# merigold.net
KiCad netlist of a schematic drawn in Altium Designer
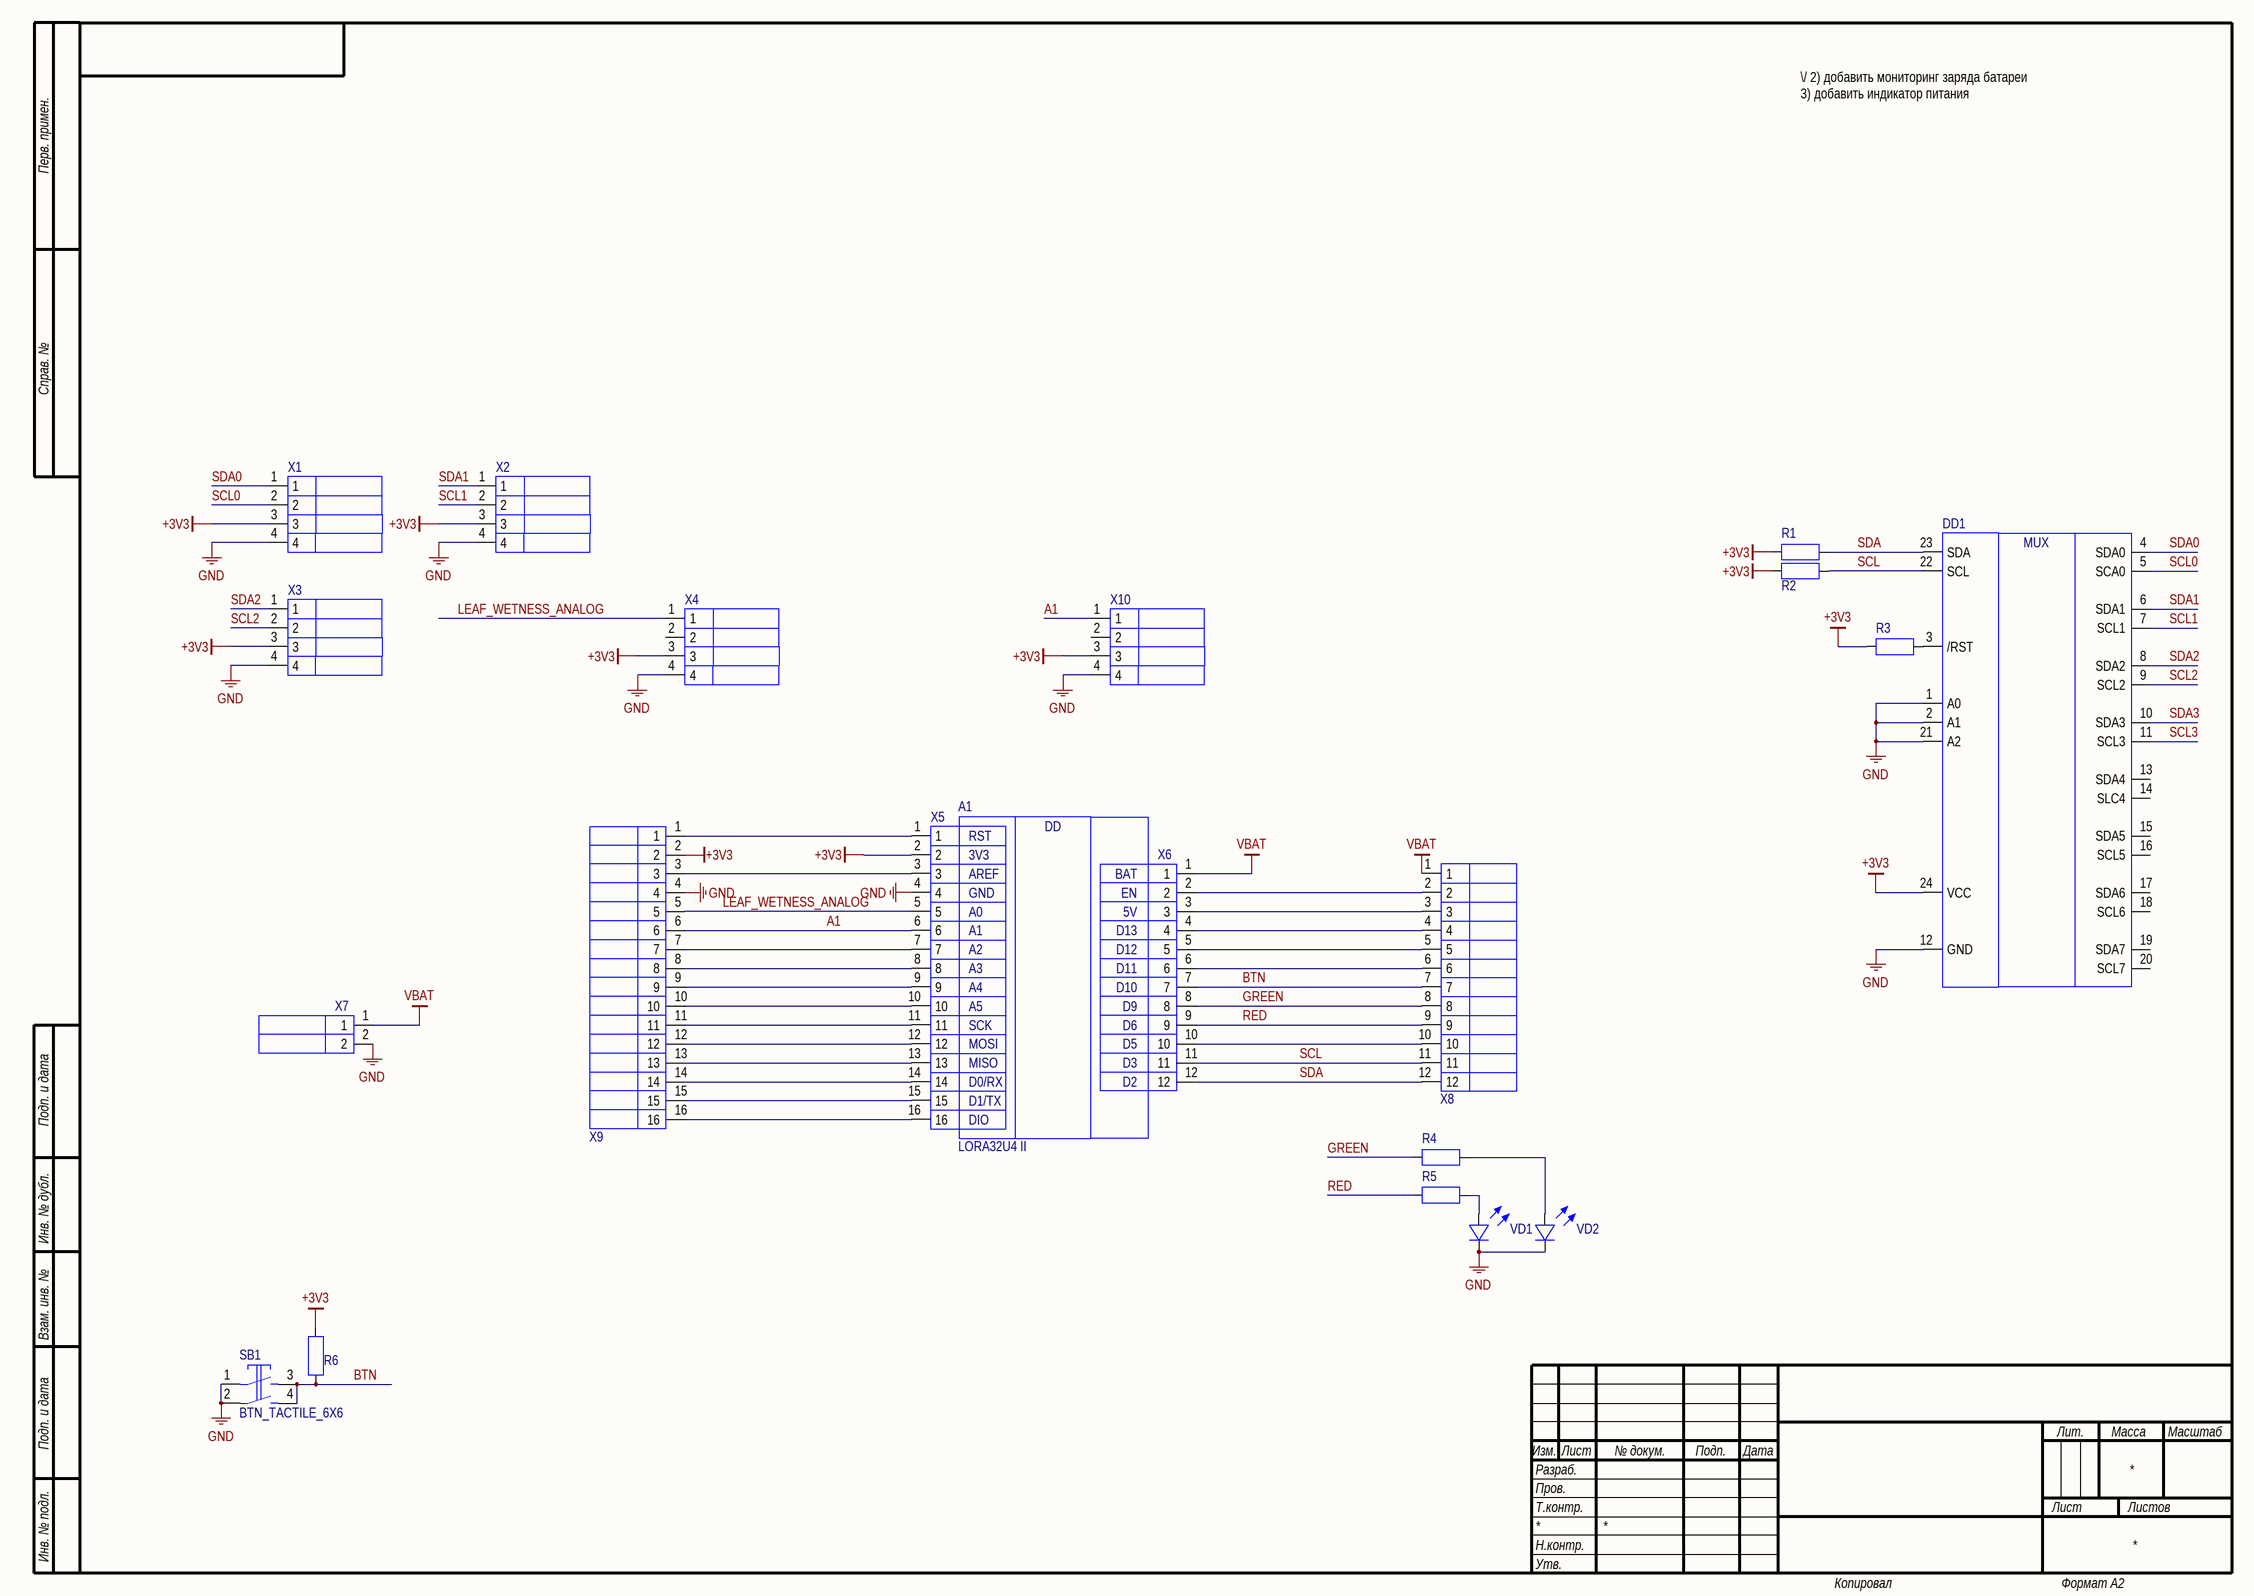
[diagram p0: merigold.SchDoc]

(export (version "E")
  (design (tool "Eeschema 10.0.6"))
  (components
    (comp (ref "A1")
      (value "LORA32U4 II")
      (footprint "LORA32U4 II")
      (description "LORA 32U4 II 868MHZ")
      (fields
        (field (name "MANUFACTURER") "BSFrance")
        (field (name "MANUFACTURER PART NUMBER") "Lora32U4 II ver 1.2")
      )
      (libsource (lib "EVALBRD") (part "LORA32U4 II"))
    )
    (comp (ref "DD1")
      (value "TCA9548A")
      (footprint "TSOP65P640X120-24M")
      (description "IC I2C SW 8CH W/RESET 24TSSOP")
      (fields
        (field (name "MANUFACTURER") "Texas Instruments")
        (field (name "MANUFACTURER PART NUMBER") "TCA9548APWR")
      )
      (libsource (lib "IC") (part "TCA9548A"))
    )
    (comp (ref "R1")
      (value "10K1206")
      (footprint "RLC:RESC3216X07N/1206")
      (description "RES SMD 10K OHM 1% 1/4W 1206")
      (fields
        (field (name "MANUFACTURER") "Panasonic")
        (field (name "MANUFACTURER PART NUMBER") "ERJ8ENF1002V")
      )
      (libsource (lib "") (part "10K1206_1"))
    )
    (comp (ref "R2")
      (value "10K1206")
      (footprint "RLC:RESC3216X07N/1206")
      (description "RES SMD 10K OHM 1% 1/4W 1206")
      (fields
        (field (name "MANUFACTURER") "Panasonic")
        (field (name "MANUFACTURER PART NUMBER") "ERJ8ENF1002V")
      )
      (libsource (lib "") (part "10K1206_1"))
    )
    (comp (ref "R3")
      (value "10K1206")
      (footprint "RLC:RESC3216X07N/1206")
      (description "RES SMD 10K OHM 1% 1/4W 1206")
      (fields
        (field (name "MANUFACTURER") "Panasonic")
        (field (name "MANUFACTURER PART NUMBER") "ERJ8ENF1002V")
      )
      (libsource (lib "") (part "10K1206_1"))
    )
    (comp (ref "R4")
      (value "200R1206")
      (footprint "RESC3216X07N/1206")
      (description "RES SMD 200 OHM 1% 1/4W 1206")
      (fields
        (field (name "MANUFACTURER PART NUMBER") "CRCW1206200RFKEA")
        (field (name "MANUFACTURER") "Vishay Dale")
      )
      (libsource (lib "R") (part "200R1206"))
    )
    (comp (ref "R5")
      (value "200R1206")
      (footprint "RESC3216X07N/1206")
      (description "RES SMD 200 OHM 1% 1/4W 1206")
      (fields
        (field (name "MANUFACTURER PART NUMBER") "CRCW1206200RFKEA")
        (field (name "MANUFACTURER") "Vishay Dale")
      )
      (libsource (lib "R") (part "200R1206"))
    )
    (comp (ref "R6")
      (value "10K1206")
      (footprint "RLC:RESC3216X07N/1206")
      (description "RES SMD 10K OHM 1% 1/4W 1206")
      (fields
        (field (name "MANUFACTURER") "Panasonic")
        (field (name "MANUFACTURER PART NUMBER") "ERJ8ENF1002V")
      )
      (libsource (lib "R") (part "10K1206"))
    )
    (comp (ref "SB1")
      (value "BTN_TACTILE_6X6")
      (footprint "BTN_TACTILE_6X6")
      (description "SWITCH TACTILE SPST-NO 0.05A 24V")
      (fields
        (field (name "MANUFACTURER") "TE Connectivity Alcoswitch")
        (field (name "MANUFACTURER PART NUMBER") "1825910-6")
      )
      (libsource (lib "SW") (part "BTN_TACTILE_6X6"))
    )
    (comp (ref "VD1")
      (value "LED_SSL-LX5093GD-TR26")
      (footprint "LED500")
      (description "LED GREEN DIFFUSED T-1 3/4 T/H")
      (fields
        (field (name "MANUFACTURER") "Lumex")
        (field (name "MANUFACTURER PART NUMBER") "SSL-LX5093GD-TR26")
      )
      (libsource (lib "D") (part "LED_SSL-LX5093GD-TR26"))
    )
    (comp (ref "VD2")
      (value "LED_SSL-LX5093GD-TR26")
      (footprint "LED500")
      (description "LED GREEN DIFFUSED T-1 3/4 T/H")
      (fields
        (field (name "MANUFACTURER") "Lumex")
        (field (name "MANUFACTURER PART NUMBER") "SSL-LX5093GD-TR26")
      )
      (libsource (lib "D") (part "LED_SSL-LX5093GD-TR26"))
    )
    (comp (ref "X1")
      (value "MOLEX_0397000904")
      (footprint "MOLEX_0397000904")
      (description "TERM BLK 4POS TOP ENTRY 5MM PCB")
      (fields (field (name "MANUFACTURER") "Molex") (field (name "MANUFACTURER PART NUMBER") "0397000904"))
      (libsource (lib "X") (part "MOLEX_0397000904"))
    )
    (comp (ref "X2")
      (value "MOLEX_0397000904")
      (footprint "MOLEX_0397000904")
      (description "TERM BLK 4POS TOP ENTRY 5MM PCB")
      (fields (field (name "MANUFACTURER") "Molex") (field (name "MANUFACTURER PART NUMBER") "0397000904"))
      (libsource (lib "X") (part "MOLEX_0397000904"))
    )
    (comp (ref "X3")
      (value "MOLEX_0397000904")
      (footprint "MOLEX_0397000904")
      (description "TERM BLK 4POS TOP ENTRY 5MM PCB")
      (fields (field (name "MANUFACTURER") "Molex") (field (name "MANUFACTURER PART NUMBER") "0397000904"))
      (libsource (lib "X") (part "MOLEX_0397000904"))
    )
    (comp (ref "X4")
      (value "MOLEX_0397000904")
      (footprint "MOLEX_0397000904")
      (description "TERM BLK 4POS TOP ENTRY 5MM PCB")
      (fields (field (name "MANUFACTURER") "Molex") (field (name "MANUFACTURER PART NUMBER") "0397000904"))
      (libsource (lib "X") (part "MOLEX_0397000904"))
    )
    (comp (ref "X5")
      (value "PLS_16_FEMALE")
      (footprint "PLS_16_FEMALE")
      (description "CONN RCPT 16POS 0.1 GOLD PCB")
      (fields
        (field (name "MANUFACTURER") "TE Connectivity AMP Connectors")
        (field (name "MANUFACTURER PART NUMBER") "1-534237-4")
      )
      (libsource (lib "X") (part "PLS_16_FEMALE"))
    )
    (comp (ref "X6")
      (value "PLS_12_FEMALE")
      (footprint "PLS_12_FEMALE")
      (description "CONN RCPT 12POS 0.1 GOLD PCB")
      (fields
        (field (name "MANUFACTURER") "TE Connectivity AMP Connectors")
        (field (name "MANUFACTURER PART NUMBER") "1-534237-0")
      )
      (libsource (lib "X") (part "PLS_12_FEMALE"))
    )
    (comp (ref "X7")
      (value "2EDGV-5.0-02P")
      (footprint "2EDGV-5.0-02P")
      (description "TERM BLOCK HDR 2POS VERT 5MM")
      (fields
        (field (name "MANUFACTURER") "Phoenix Contact")
        (field (name "MANUFACTURER PART NUMBER") "1753437")
      )
      (libsource (lib "X") (part "2EDGV-5.0-02P"))
    )
    (comp (ref "X8")
      (value "PLS_12_FEMALE")
      (footprint "PLS_12_FEMALE")
      (description "CONN RCPT 12POS 0.1 GOLD PCB")
      (fields
        (field (name "MANUFACTURER") "TE Connectivity AMP Connectors")
        (field (name "MANUFACTURER PART NUMBER") "1-534237-0")
      )
      (libsource (lib "X") (part "PLS_12_FEMALE"))
    )
    (comp (ref "X9")
      (value "PLS_16_FEMALE")
      (footprint "PLS_16_FEMALE")
      (description "CONN RCPT 16POS 0.1 GOLD PCB")
      (fields
        (field (name "MANUFACTURER") "TE Connectivity AMP Connectors")
        (field (name "MANUFACTURER PART NUMBER") "1-534237-4")
      )
      (libsource (lib "X") (part "PLS_16_FEMALE"))
    )
    (comp (ref "X10")
      (value "MOLEX_0397000904")
      (footprint "MOLEX_0397000904")
      (description "TERM BLK 4POS TOP ENTRY 5MM PCB")
      (fields (field (name "MANUFACTURER") "Molex") (field (name "MANUFACTURER PART NUMBER") "0397000904"))
      (libsource (lib "X") (part "MOLEX_0397000904"))
    )
  )
  (nets
    (net (code "1") (name "+3V3") (class "Default")
      (node (ref "DD1") (pin "24") (pinfunction "VCC_24") (pintype "passive"))
      (node (ref "R1") (pin "2") (pinfunction "2_2") (pintype "passive"))
      (node (ref "R2") (pin "2") (pinfunction "2_2") (pintype "passive"))
      (node (ref "R3") (pin "2") (pinfunction "2_2") (pintype "passive"))
      (node (ref "R6") (pin "2") (pinfunction "2_2") (pintype "passive"))
      (node (ref "X1") (pin "3") (pinfunction "3_3") (pintype "passive"))
      (node (ref "X10") (pin "3") (pinfunction "3_3") (pintype "passive"))
      (node (ref "X2") (pin "3") (pinfunction "3_3") (pintype "passive"))
      (node (ref "X3") (pin "3") (pinfunction "3_3") (pintype "passive"))
      (node (ref "X4") (pin "3") (pinfunction "3_3") (pintype "passive"))
      (node (ref "X5") (pin "2") (pinfunction "2_2") (pintype "passive"))
      (node (ref "X9") (pin "2") (pinfunction "2_2") (pintype "passive"))
    )
    (net (code "2") (name "/A1") (class "Default")
      (node (ref "X10") (pin "1") (pinfunction "1_1") (pintype "passive"))
      (node (ref "X5") (pin "6") (pinfunction "6_6") (pintype "passive"))
      (node (ref "X9") (pin "6") (pinfunction "6_6") (pintype "passive"))
    )
    (net (code "3") (name "/BTN") (class "Default")
      (node (ref "R6") (pin "1") (pinfunction "1_1") (pintype "passive"))
      (node (ref "SB1") (pin "3") (pinfunction "3_3") (pintype "passive"))
      (node (ref "SB1") (pin "4") (pinfunction "4_4") (pintype "passive"))
      (node (ref "X6") (pin "7") (pinfunction "7_7") (pintype "passive"))
      (node (ref "X8") (pin "7") (pinfunction "7_7") (pintype "passive"))
    )
    (net (code "4") (name "/GREEN") (class "Default")
      (node (ref "R4") (pin "2") (pinfunction "2_2") (pintype "passive"))
      (node (ref "X6") (pin "8") (pinfunction "8_8") (pintype "passive"))
      (node (ref "X8") (pin "8") (pinfunction "8_8") (pintype "passive"))
    )
    (net (code "5") (name "/LEAF_WETNESS_ANALOG") (class "Default")
      (node (ref "X4") (pin "1") (pinfunction "1_1") (pintype "passive"))
      (node (ref "X5") (pin "5") (pinfunction "5_5") (pintype "passive"))
      (node (ref "X9") (pin "5") (pinfunction "5_5") (pintype "passive"))
    )
    (net (code "6") (name "/RED") (class "Default")
      (node (ref "R5") (pin "2") (pinfunction "2_2") (pintype "passive"))
      (node (ref "X6") (pin "9") (pinfunction "9_9") (pintype "passive"))
      (node (ref "X8") (pin "9") (pinfunction "9_9") (pintype "passive"))
    )
    (net (code "7") (name "/SCL") (class "Default")
      (node (ref "DD1") (pin "22") (pinfunction "SCL_22") (pintype "passive"))
      (node (ref "R2") (pin "1") (pinfunction "1_1") (pintype "passive"))
      (node (ref "X6") (pin "11") (pinfunction "11_11") (pintype "passive"))
      (node (ref "X8") (pin "11") (pinfunction "11_11") (pintype "passive"))
    )
    (net (code "8") (name "/SCL0") (class "Default")
      (node (ref "DD1") (pin "5") (pinfunction "SCA0_5") (pintype "passive"))
      (node (ref "X1") (pin "2") (pinfunction "2_2") (pintype "passive"))
    )
    (net (code "9") (name "/SCL1") (class "Default")
      (node (ref "DD1") (pin "7") (pinfunction "SCL1_7") (pintype "passive"))
      (node (ref "X2") (pin "2") (pinfunction "2_2") (pintype "passive"))
    )
    (net (code "10") (name "/SCL2") (class "Default")
      (node (ref "DD1") (pin "9") (pinfunction "SCL2_9") (pintype "passive"))
      (node (ref "X3") (pin "2") (pinfunction "2_2") (pintype "passive"))
    )
    (net (code "11") (name "/SCL3") (class "Default")
      (node (ref "DD1") (pin "11") (pinfunction "SCL3_11") (pintype "passive"))
    )
    (net (code "12") (name "/SDA") (class "Default")
      (node (ref "DD1") (pin "23") (pinfunction "SDA_23") (pintype "passive"))
      (node (ref "R1") (pin "1") (pinfunction "1_1") (pintype "passive"))
      (node (ref "X6") (pin "12") (pinfunction "12_12") (pintype "passive"))
      (node (ref "X8") (pin "12") (pinfunction "12_12") (pintype "passive"))
    )
    (net (code "13") (name "/SDA0") (class "Default")
      (node (ref "DD1") (pin "4") (pinfunction "SDA0_4") (pintype "passive"))
      (node (ref "X1") (pin "1") (pinfunction "1_1") (pintype "passive"))
    )
    (net (code "14") (name "/SDA1") (class "Default")
      (node (ref "DD1") (pin "6") (pinfunction "SDA1_6") (pintype "passive"))
      (node (ref "X2") (pin "1") (pinfunction "1_1") (pintype "passive"))
    )
    (net (code "15") (name "/SDA2") (class "Default")
      (node (ref "DD1") (pin "8") (pinfunction "SDA2_8") (pintype "passive"))
      (node (ref "X3") (pin "1") (pinfunction "1_1") (pintype "passive"))
    )
    (net (code "16") (name "/SDA3") (class "Default")
      (node (ref "DD1") (pin "10") (pinfunction "SDA3_10") (pintype "passive"))
    )
    (net (code "17") (name "GND") (class "Default")
      (node (ref "DD1") (pin "1") (pinfunction "A0_1") (pintype "passive"))
      (node (ref "DD1") (pin "12") (pinfunction "GND_12") (pintype "passive"))
      (node (ref "DD1") (pin "2") (pinfunction "A1_2") (pintype "passive"))
      (node (ref "DD1") (pin "21") (pinfunction "A2_21") (pintype "passive"))
      (node (ref "SB1") (pin "1") (pinfunction "1_1") (pintype "passive"))
      (node (ref "SB1") (pin "2") (pinfunction "2_2") (pintype "passive"))
      (node (ref "VD1") (pin "K") (pinfunction "K_K") (pintype "passive"))
      (node (ref "VD2") (pin "K") (pinfunction "K_K") (pintype "passive"))
      (node (ref "X1") (pin "4") (pinfunction "4_4") (pintype "passive"))
      (node (ref "X10") (pin "4") (pinfunction "4_4") (pintype "passive"))
      (node (ref "X2") (pin "4") (pinfunction "4_4") (pintype "passive"))
      (node (ref "X3") (pin "4") (pinfunction "4_4") (pintype "passive"))
      (node (ref "X4") (pin "4") (pinfunction "4_4") (pintype "passive"))
      (node (ref "X5") (pin "4") (pinfunction "4_4") (pintype "passive"))
      (node (ref "X7") (pin "2") (pinfunction "2_2") (pintype "passive"))
      (node (ref "X9") (pin "4") (pinfunction "4_4") (pintype "passive"))
    )
    (net (code "18") (name "Net-(DD1-{slash}RST)") (class "Default")
      (node (ref "DD1") (pin "3") (pinfunction "/RST_3") (pintype "passive"))
      (node (ref "R3") (pin "1") (pinfunction "1_1") (pintype "passive"))
    )
    (net (code "19") (name "Net-(R4-Pad1)") (class "Default")
      (node (ref "R4") (pin "1") (pinfunction "1_1") (pintype "passive"))
      (node (ref "VD2") (pin "A") (pinfunction "A_A") (pintype "passive"))
    )
    (net (code "20") (name "Net-(R5-Pad1)") (class "Default")
      (node (ref "R5") (pin "1") (pinfunction "1_1") (pintype "passive"))
      (node (ref "VD1") (pin "A") (pinfunction "A_A") (pintype "passive"))
    )
    (net (code "21") (name "Net-(X5-Pad1)") (class "Default")
      (node (ref "X5") (pin "1") (pinfunction "1_1") (pintype "passive"))
      (node (ref "X9") (pin "1") (pinfunction "1_1") (pintype "passive"))
    )
    (net (code "22") (name "Net-(X5-Pad3)") (class "Default")
      (node (ref "X5") (pin "3") (pinfunction "3_3") (pintype "passive"))
      (node (ref "X9") (pin "3") (pinfunction "3_3") (pintype "passive"))
    )
    (net (code "23") (name "Net-(X5-Pad7)") (class "Default")
      (node (ref "X5") (pin "7") (pinfunction "7_7") (pintype "passive"))
      (node (ref "X9") (pin "7") (pinfunction "7_7") (pintype "passive"))
    )
    (net (code "24") (name "Net-(X5-Pad8)") (class "Default")
      (node (ref "X5") (pin "8") (pinfunction "8_8") (pintype "passive"))
      (node (ref "X9") (pin "8") (pinfunction "8_8") (pintype "passive"))
    )
    (net (code "25") (name "Net-(X5-Pad9)") (class "Default")
      (node (ref "X5") (pin "9") (pinfunction "9_9") (pintype "passive"))
      (node (ref "X9") (pin "9") (pinfunction "9_9") (pintype "passive"))
    )
    (net (code "26") (name "Net-(X5-Pad10)") (class "Default")
      (node (ref "X5") (pin "10") (pinfunction "10_10") (pintype "passive"))
      (node (ref "X9") (pin "10") (pinfunction "10_10") (pintype "passive"))
    )
    (net (code "27") (name "Net-(X5-Pad11)") (class "Default")
      (node (ref "X5") (pin "11") (pinfunction "11_11") (pintype "passive"))
      (node (ref "X9") (pin "11") (pinfunction "11_11") (pintype "passive"))
    )
    (net (code "28") (name "Net-(X5-Pad12)") (class "Default")
      (node (ref "X5") (pin "12") (pinfunction "12_12") (pintype "passive"))
      (node (ref "X9") (pin "12") (pinfunction "12_12") (pintype "passive"))
    )
    (net (code "29") (name "Net-(X5-Pad13)") (class "Default")
      (node (ref "X5") (pin "13") (pinfunction "13_13") (pintype "passive"))
      (node (ref "X9") (pin "13") (pinfunction "13_13") (pintype "passive"))
    )
    (net (code "30") (name "Net-(X5-Pad14)") (class "Default")
      (node (ref "X5") (pin "14") (pinfunction "14_14") (pintype "passive"))
      (node (ref "X9") (pin "14") (pinfunction "14_14") (pintype "passive"))
    )
    (net (code "31") (name "Net-(X5-Pad15)") (class "Default")
      (node (ref "X5") (pin "15") (pinfunction "15_15") (pintype "passive"))
      (node (ref "X9") (pin "15") (pinfunction "15_15") (pintype "passive"))
    )
    (net (code "32") (name "Net-(X5-Pad16)") (class "Default")
      (node (ref "X5") (pin "16") (pinfunction "16_16") (pintype "passive"))
      (node (ref "X9") (pin "16") (pinfunction "16_16") (pintype "passive"))
    )
    (net (code "33") (name "Net-(X6-Pad2)") (class "Default")
      (node (ref "X6") (pin "2") (pinfunction "2_2") (pintype "passive"))
      (node (ref "X8") (pin "2") (pinfunction "2_2") (pintype "passive"))
    )
    (net (code "34") (name "Net-(X6-Pad3)") (class "Default")
      (node (ref "X6") (pin "3") (pinfunction "3_3") (pintype "passive"))
      (node (ref "X8") (pin "3") (pinfunction "3_3") (pintype "passive"))
    )
    (net (code "35") (name "Net-(X6-Pad4)") (class "Default")
      (node (ref "X6") (pin "4") (pinfunction "4_4") (pintype "passive"))
      (node (ref "X8") (pin "4") (pinfunction "4_4") (pintype "passive"))
    )
    (net (code "36") (name "Net-(X6-Pad5)") (class "Default")
      (node (ref "X6") (pin "5") (pinfunction "5_5") (pintype "passive"))
      (node (ref "X8") (pin "5") (pinfunction "5_5") (pintype "passive"))
    )
    (net (code "37") (name "Net-(X6-Pad6)") (class "Default")
      (node (ref "X6") (pin "6") (pinfunction "6_6") (pintype "passive"))
      (node (ref "X8") (pin "6") (pinfunction "6_6") (pintype "passive"))
    )
    (net (code "38") (name "Net-(X6-Pad10)") (class "Default")
      (node (ref "X6") (pin "10") (pinfunction "10_10") (pintype "passive"))
      (node (ref "X8") (pin "10") (pinfunction "10_10") (pintype "passive"))
    )
    (net (code "39") (name "VBAT") (class "Default")
      (node (ref "X6") (pin "1") (pinfunction "1_1") (pintype "passive"))
      (node (ref "X7") (pin "1") (pinfunction "1_1") (pintype "passive"))
      (node (ref "X8") (pin "1") (pinfunction "1_1") (pintype "passive"))
    )
    (net (code "40") (name "unconnected-(DD1-SCL5-Pad16)") (class "Default")
      (node (ref "DD1") (pin "16") (pinfunction "SCL5_16") (pintype "passive"))
    )
    (net (code "41") (name "unconnected-(DD1-SCL6-Pad18)") (class "Default")
      (node (ref "DD1") (pin "18") (pinfunction "SCL6_18") (pintype "passive"))
    )
    (net (code "42") (name "unconnected-(DD1-SCL7-Pad20)") (class "Default")
      (node (ref "DD1") (pin "20") (pinfunction "SCL7_20") (pintype "passive"))
    )
    (net (code "43") (name "unconnected-(DD1-SDA4-Pad13)") (class "Default")
      (node (ref "DD1") (pin "13") (pinfunction "SDA4_13") (pintype "passive"))
    )
    (net (code "44") (name "unconnected-(DD1-SDA5-Pad15)") (class "Default")
      (node (ref "DD1") (pin "15") (pinfunction "SDA5_15") (pintype "passive"))
    )
    (net (code "45") (name "unconnected-(DD1-SDA6-Pad17)") (class "Default")
      (node (ref "DD1") (pin "17") (pinfunction "SDA6_17") (pintype "passive"))
    )
    (net (code "46") (name "unconnected-(DD1-SDA7-Pad19)") (class "Default")
      (node (ref "DD1") (pin "19") (pinfunction "SDA7_19") (pintype "passive"))
    )
    (net (code "47") (name "unconnected-(DD1-SLC4-Pad14)") (class "Default")
      (node (ref "DD1") (pin "14") (pinfunction "SLC4_14") (pintype "passive"))
    )
    (net (code "48") (name "unconnected-(X4-Pad2)") (class "Default")
      (node (ref "X4") (pin "2") (pinfunction "2_2") (pintype "passive"))
    )
    (net (code "49") (name "unconnected-(X10-Pad2)") (class "Default")
      (node (ref "X10") (pin "2") (pinfunction "2_2") (pintype "passive"))
    )
  )
)
